# LISN_Mate.net
KiCad netlist of a schematic drawn in Altium Designer
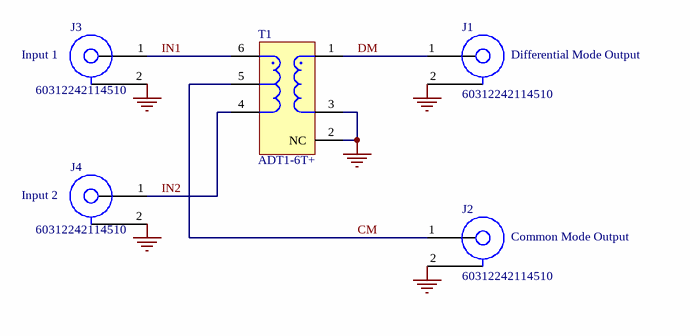
[diagram p0: LISN_Mate.SchDoc]

(export (version "E")
  (design (tool "Eeschema 10.0.6"))
  (components
    (comp (ref "J1")
      (value "60312242114510")
      (footprint "LISN_Mate:60312242114510")
      (description "Connector - SMA Socket, Right-Angle, PCB Edge Mount, 50 ohm")
      (libsource (lib "LISN_Mate") (part "RF-CONNECTOR"))
    )
    (comp (ref "J2")
      (value "60312242114510")
      (footprint "LISN_Mate:60312242114510")
      (description "Connector - SMA Socket, Right-Angle, PCB Edge Mount, 50 ohm")
      (libsource (lib "LISN_Mate") (part "RF-CONNECTOR"))
    )
    (comp (ref "J3")
      (value "60312242114510")
      (footprint "LISN_Mate:60312242114510")
      (description "Connector - SMA Socket, Right-Angle, PCB Edge Mount, 50 ohm")
      (libsource (lib "LISN_Mate") (part "RF-CONNECTOR"))
    )
    (comp (ref "J4")
      (value "60312242114510")
      (footprint "LISN_Mate:60312242114510")
      (description "Connector - SMA Socket, Right-Angle, PCB Edge Mount, 50 ohm")
      (libsource (lib "LISN_Mate") (part "RF-CONNECTOR"))
    )
    (comp (ref "T1")
      (value "ADT1-6T+")
      (footprint "LISN_Mate:FP-CD637")
      (description "RF Transformer - ADT1-6T+")
      (libsource (lib "LISN_Mate") (part "Transformer 1{colon}1 Centre Tap with NC Pin"))
    )
  )
  (nets
    (net (code "1") (name "/CM") (class "Default")
      (node (ref "J2") (pin "1") (pinfunction "RF_1") (pintype "passive"))
      (node (ref "T1") (pin "5") (pinfunction "5_5") (pintype "passive"))
    )
    (net (code "2") (name "/DM") (class "Default")
      (node (ref "J1") (pin "1") (pinfunction "RF_1") (pintype "passive"))
      (node (ref "T1") (pin "1") (pinfunction "1_1") (pintype "passive"))
    )
    (net (code "3") (name "/IN1") (class "Default")
      (node (ref "J3") (pin "1") (pinfunction "RF_1") (pintype "passive"))
      (node (ref "T1") (pin "6") (pinfunction "6_6") (pintype "passive"))
    )
    (net (code "4") (name "/IN2") (class "Default")
      (node (ref "J4") (pin "1") (pinfunction "RF_1") (pintype "passive"))
      (node (ref "T1") (pin "4") (pinfunction "4_4") (pintype "passive"))
    )
    (net (code "5") (name "GND") (class "Default")
      (node (ref "J1") (pin "2") (pinfunction "RF_GND_2") (pintype "power_in"))
      (node (ref "J2") (pin "2") (pinfunction "RF_GND_2") (pintype "power_in"))
      (node (ref "J3") (pin "2") (pinfunction "RF_GND_2") (pintype "power_in"))
      (node (ref "J4") (pin "2") (pinfunction "RF_GND_2") (pintype "power_in"))
      (node (ref "T1") (pin "2") (pinfunction "NC_2") (pintype "passive"))
      (node (ref "T1") (pin "3") (pinfunction "3_3") (pintype "passive"))
    )
  )
)
